# PassVault.net
KiCad netlist of a schematic drawn in EAGLE
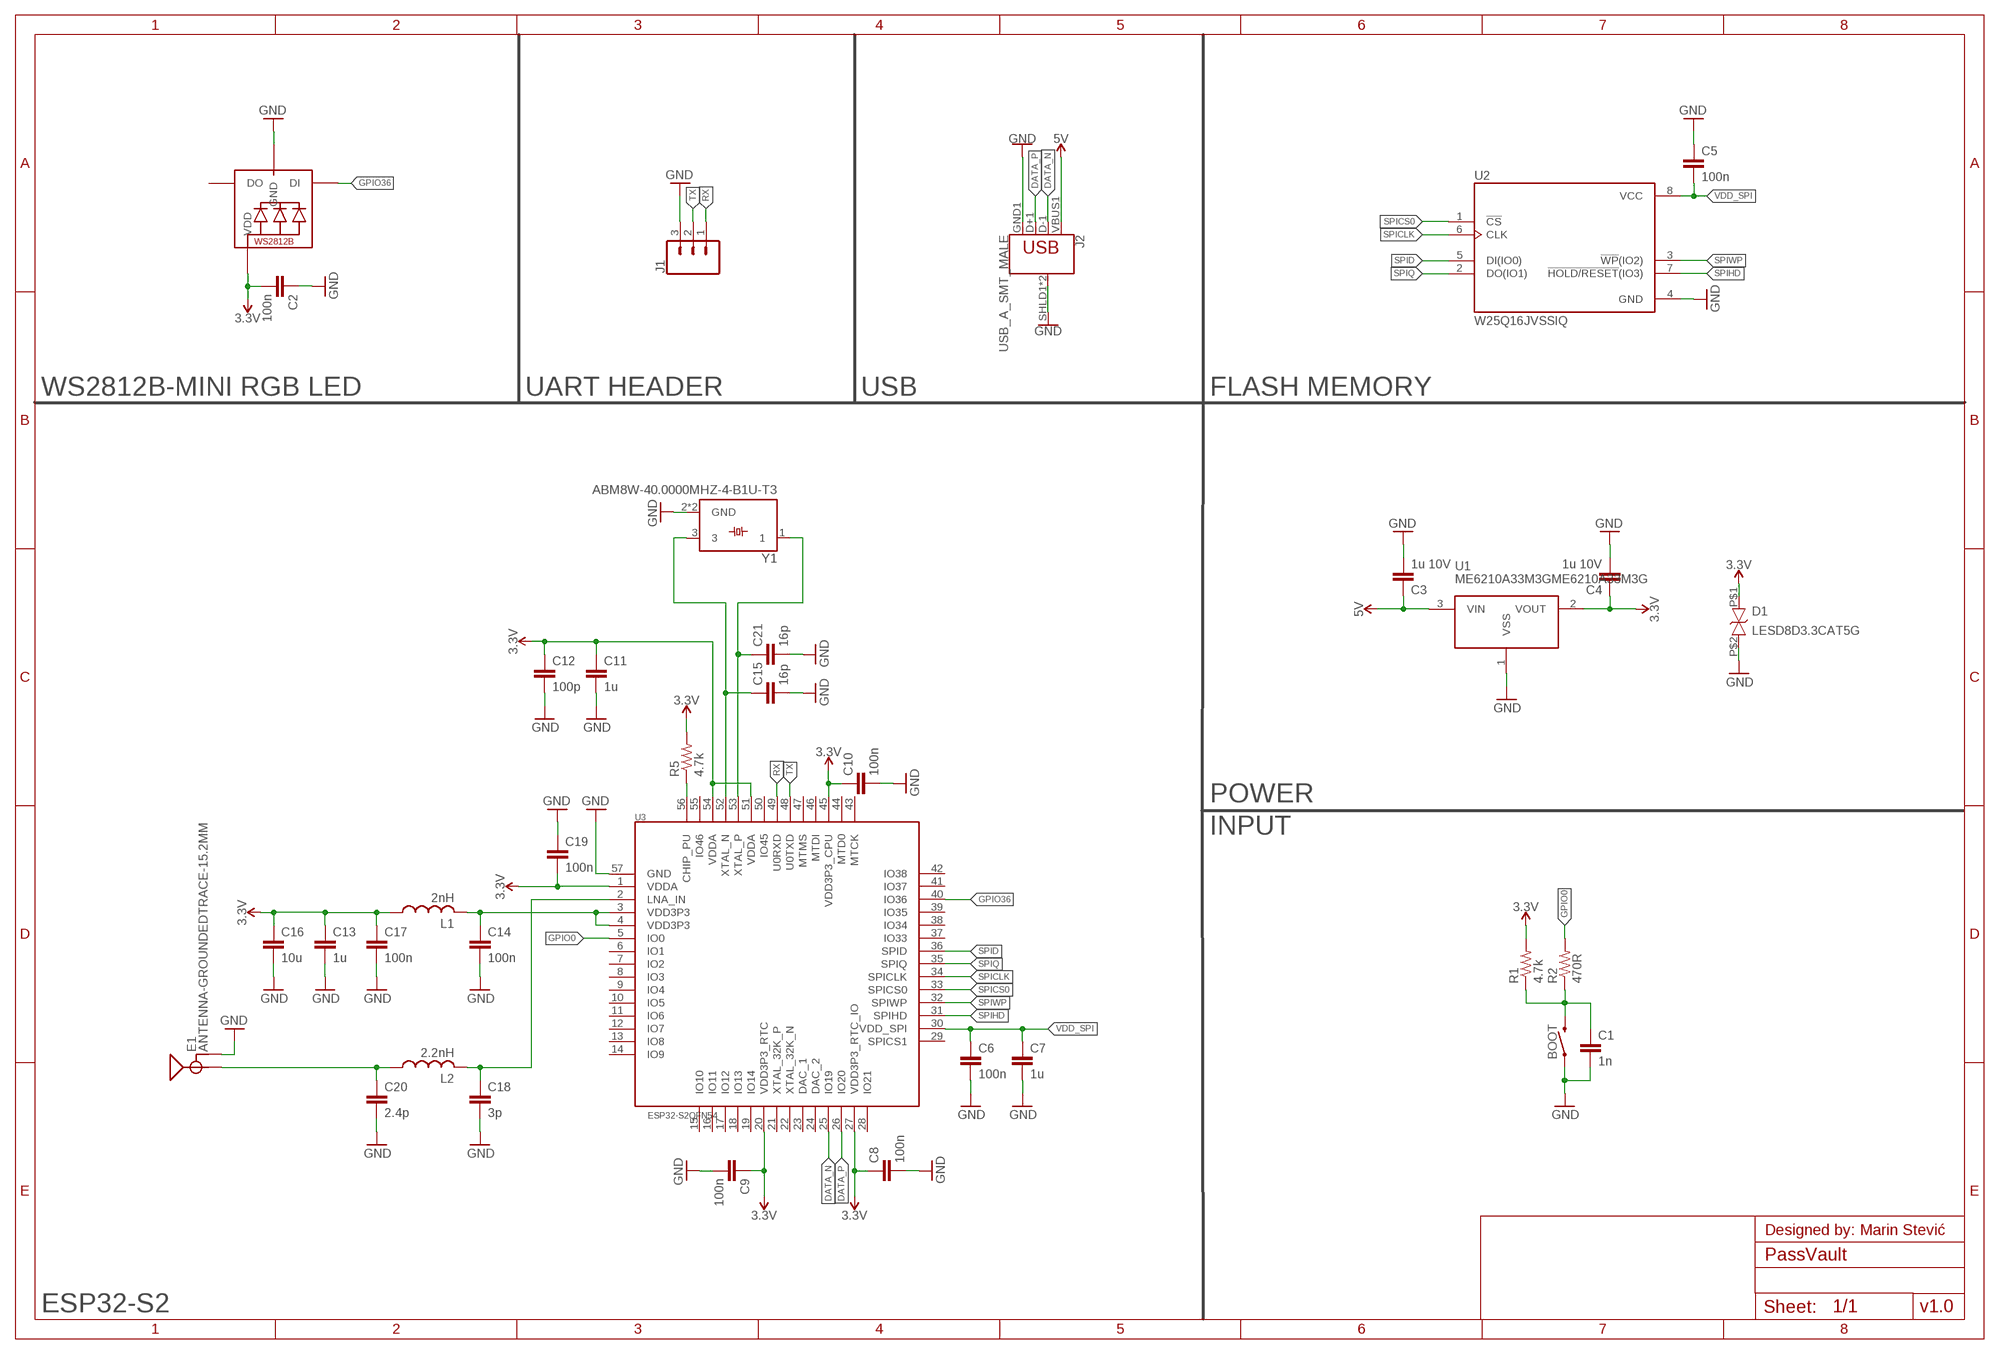
[diagram p0: schematic, sheet 1]

(export (version "E")
  (design (tool "Eeschema 10.0.6"))
  (components
    (comp (ref "BOOT")
      (value "MOMENTARY-SWITCH-SPST-SMD-12MM")
      (footprint "eagle-import:TACTILE_SWITCH_SMD_12MM")
      (libsource (lib "eagle-import") (part "MOMENTARY-SWITCH-SPST-SMD-12MM"))
    )
    (comp (ref "C1")
      (value "1n")
      (footprint "eagle-import:C0201")
      (libsource (lib "eagle-import") (part "C-EUC0201"))
    )
    (comp (ref "C2")
      (value "100n")
      (footprint "eagle-import:C0402")
      (libsource (lib "eagle-import") (part "C-EUC0402"))
    )
    (comp (ref "C3")
      (value "1u 10V")
      (footprint "eagle-import:C0402")
      (libsource (lib "eagle-import") (part "C-EUC0402"))
    )
    (comp (ref "C4")
      (value "1u 10V")
      (footprint "eagle-import:C0402")
      (libsource (lib "eagle-import") (part "C-EUC0402"))
    )
    (comp (ref "C5")
      (value "100n")
      (footprint "eagle-import:C0201")
      (libsource (lib "eagle-import") (part "C-EUC0201"))
    )
    (comp (ref "C6")
      (value "100n")
      (footprint "eagle-import:C0201")
      (libsource (lib "eagle-import") (part "C-EUC0201"))
    )
    (comp (ref "C7")
      (value "1u")
      (footprint "eagle-import:C0201")
      (libsource (lib "eagle-import") (part "C-EUC0201"))
    )
    (comp (ref "C8")
      (value "100n")
      (footprint "eagle-import:C0201")
      (libsource (lib "eagle-import") (part "C-EUC0201"))
    )
    (comp (ref "C9")
      (value "100n")
      (footprint "eagle-import:C0201")
      (libsource (lib "eagle-import") (part "C-EUC0201"))
    )
    (comp (ref "C10")
      (value "100n")
      (footprint "eagle-import:C0201")
      (libsource (lib "eagle-import") (part "C-EUC0201"))
    )
    (comp (ref "C11")
      (value "1u")
      (footprint "eagle-import:C0201")
      (libsource (lib "eagle-import") (part "C-EUC0201"))
    )
    (comp (ref "C12")
      (value "100p")
      (footprint "eagle-import:C0201")
      (libsource (lib "eagle-import") (part "C-EUC0201"))
    )
    (comp (ref "C13")
      (value "1u")
      (footprint "eagle-import:C0201")
      (libsource (lib "eagle-import") (part "C-EUC0201"))
    )
    (comp (ref "C14")
      (value "100n")
      (footprint "eagle-import:C0201")
      (libsource (lib "eagle-import") (part "C-EUC0201"))
    )
    (comp (ref "C15")
      (value "16p")
      (footprint "eagle-import:C0201")
      (libsource (lib "eagle-import") (part "C-EUC0201"))
    )
    (comp (ref "C16")
      (value "10u")
      (footprint "eagle-import:C0402")
      (libsource (lib "eagle-import") (part "C-EUC0402"))
    )
    (comp (ref "C17")
      (value "100n")
      (footprint "eagle-import:C0201")
      (libsource (lib "eagle-import") (part "C-EUC0201"))
    )
    (comp (ref "C18")
      (value "3p")
      (footprint "eagle-import:C0201")
      (libsource (lib "eagle-import") (part "C-EUC0201"))
    )
    (comp (ref "C19")
      (value "100n")
      (footprint "eagle-import:C0201")
      (libsource (lib "eagle-import") (part "C-EUC0201"))
    )
    (comp (ref "C20")
      (value "2.4p")
      (footprint "eagle-import:C0201")
      (libsource (lib "eagle-import") (part "C-EUC0201"))
    )
    (comp (ref "C21")
      (value "16p")
      (footprint "eagle-import:C0201")
      (libsource (lib "eagle-import") (part "C-EUC0201"))
    )
    (comp (ref "D1")
      (value "LESD8D3.3CAT5G")
      (footprint "eagle-import:LESD8D3.3CAT5G")
      (libsource (lib "eagle-import") (part "LESD8D3.3CAT5G"))
    )
    (comp (ref "E1")
      (value "ANTENNA-GROUNDEDTRACE-15.2MM")
      (footprint "eagle-import:TRACE_ANTENNA_2.4GHZ_15.2MM")
      (libsource (lib "eagle-import") (part "ANTENNA-GROUNDEDTRACE-15.2MM"))
    )
    (comp (ref "J1")
      (value "CONN_03")
      (footprint "eagle-import:1X03")
      (libsource (lib "eagle-import") (part "CONN_03"))
    )
    (comp (ref "J2")
      (value "USB_A_SMT_MALE")
      (footprint "eagle-import:USB-A-SMT-MALE")
      (libsource (lib "eagle-import") (part "USB_A_SMT_MALE"))
    )
    (comp (ref "L1")
      (value "2nH")
      (footprint "eagle-import:L0201")
      (libsource (lib "eagle-import") (part "L-USL0201"))
    )
    (comp (ref "L2")
      (value "2.2nH")
      (footprint "eagle-import:L0201")
      (libsource (lib "eagle-import") (part "L-USL0201"))
    )
    (comp (ref "LED1")
      (value "WS2812B3535")
      (footprint "eagle-import:LED3535")
      (fields (field (name "MF") "SparkFun Electronics") (field (name "MP") "WS2812B"))
      (libsource (lib "eagle-import") (part "WS2812B3535"))
    )
    (comp (ref "R1")
      (value "4.7k")
      (footprint "eagle-import:R0201")
      (libsource (lib "eagle-import") (part "R-US_R0201"))
    )
    (comp (ref "R2")
      (value "470R")
      (footprint "eagle-import:R0201")
      (libsource (lib "eagle-import") (part "R-US_R0201"))
    )
    (comp (ref "R5")
      (value "4.7k")
      (footprint "eagle-import:R0201")
      (libsource (lib "eagle-import") (part "R-US_R0201"))
    )
    (comp (ref "U1")
      (value "ME6210A33M3GME6210A33M3G")
      (footprint "eagle-import:SOT95P280X110-3N")
      (libsource (lib "eagle-import") (part "ME6210A33M3GME6210A33M3G"))
    )
    (comp (ref "U2")
      (value "W25Q16JVSSIQ")
      (footprint "eagle-import:SOIC127P790X216-8N")
      (fields (field (name "MF") "Winbond Electronics"))
      (libsource (lib "eagle-import") (part "W25Q16JVSSIQ"))
    )
    (comp (ref "U3")
      (value "ESP32-S2QFN54")
      (footprint "eagle-import:QFN40P700X700X90-57T400N")
      (fields (field (name "MF") "Espressif Systems") (field (name "MP") "ESP32-S2"))
      (libsource (lib "eagle-import") (part "ESP32-S2QFN54"))
    )
    (comp (ref "Y1")
      (value "ABM8W-40.0000MHZ-4-B1U-T3")
      (footprint "eagle-import:OSCSC320X250X100N")
      (fields (field (name "MF") "Abracon"))
      (libsource (lib "eagle-import") (part "ABM8W-40.0000MHZ-4-B1U-T3"))
    )
  )
  (nets
    (net (code "1") (name "3.3V") (class "Default")
      (node (ref "C10") (pin "1") (pinfunction "1_1") (pintype "passive"))
      (node (ref "C11") (pin "1") (pinfunction "1_1") (pintype "passive"))
      (node (ref "C12") (pin "1") (pinfunction "1_1") (pintype "passive"))
      (node (ref "C13") (pin "1") (pinfunction "1_1") (pintype "passive"))
      (node (ref "C16") (pin "1") (pinfunction "1_1") (pintype "passive"))
      (node (ref "C17") (pin "1") (pinfunction "1_1") (pintype "passive"))
      (node (ref "C19") (pin "2") (pinfunction "2_2") (pintype "passive"))
      (node (ref "C2") (pin "2") (pinfunction "2_2") (pintype "passive"))
      (node (ref "C4") (pin "1") (pinfunction "1_1") (pintype "passive"))
      (node (ref "C8") (pin "1") (pinfunction "1_1") (pintype "passive"))
      (node (ref "C9") (pin "1") (pinfunction "1_1") (pintype "passive"))
      (node (ref "D1") (pin "P$1") (pinfunction "P$1_P$1") (pintype "bidirectional"))
      (node (ref "L1") (pin "1") (pinfunction "1_1") (pintype "passive"))
      (node (ref "LED1") (pin "1") (pinfunction "VDD_1") (pintype "power_in"))
      (node (ref "R1") (pin "2") (pinfunction "2_2") (pintype "passive"))
      (node (ref "R5") (pin "2") (pinfunction "2_2") (pintype "passive"))
      (node (ref "U1") (pin "2") (pinfunction "VOUT_2") (pintype "bidirectional"))
      (node (ref "U3") (pin "1") (pinfunction "VDDA_1") (pintype "power_in"))
      (node (ref "U3") (pin "20") (pinfunction "VDD3P3_RTC_20") (pintype "power_in"))
      (node (ref "U3") (pin "27") (pinfunction "VDD3P3_RTC_IO_27") (pintype "power_in"))
      (node (ref "U3") (pin "45") (pinfunction "VDD3P3_CPU_45") (pintype "power_in"))
      (node (ref "U3") (pin "51") (pinfunction "VDDA_51") (pintype "power_in"))
      (node (ref "U3") (pin "54") (pinfunction "VDDA_54") (pintype "power_in"))
    )
    (net (code "2") (name "5V") (class "Default")
      (node (ref "C3") (pin "1") (pinfunction "1_1") (pintype "passive"))
      (node (ref "J2") (pin "VBUS1") (pinfunction "VBUS_VBUS1") (pintype "power_in"))
      (node (ref "U1") (pin "3") (pinfunction "VIN_3") (pintype "bidirectional"))
    )
    (net (code "3") (name "DATA_N") (class "Default")
      (node (ref "J2") (pin "D-1") (pinfunction "D-_D-1") (pintype "bidirectional"))
      (node (ref "U3") (pin "25") (pinfunction "IO19_25") (pintype "bidirectional"))
    )
    (net (code "4") (name "DATA_P") (class "Default")
      (node (ref "J2") (pin "D+1") (pinfunction "D+_D+1") (pintype "bidirectional"))
      (node (ref "U3") (pin "26") (pinfunction "IO20_26") (pintype "bidirectional"))
    )
    (net (code "5") (name "GND") (class "Default")
      (node (ref "BOOT") (pin "1") (pinfunction "1_1") (pintype "passive"))
      (node (ref "C1") (pin "2") (pinfunction "2_2") (pintype "passive"))
      (node (ref "C10") (pin "2") (pinfunction "2_2") (pintype "passive"))
      (node (ref "C11") (pin "2") (pinfunction "2_2") (pintype "passive"))
      (node (ref "C12") (pin "2") (pinfunction "2_2") (pintype "passive"))
      (node (ref "C13") (pin "2") (pinfunction "2_2") (pintype "passive"))
      (node (ref "C14") (pin "2") (pinfunction "2_2") (pintype "passive"))
      (node (ref "C15") (pin "2") (pinfunction "2_2") (pintype "passive"))
      (node (ref "C16") (pin "2") (pinfunction "2_2") (pintype "passive"))
      (node (ref "C17") (pin "2") (pinfunction "2_2") (pintype "passive"))
      (node (ref "C18") (pin "2") (pinfunction "2_2") (pintype "passive"))
      (node (ref "C19") (pin "1") (pinfunction "1_1") (pintype "passive"))
      (node (ref "C2") (pin "1") (pinfunction "1_1") (pintype "passive"))
      (node (ref "C20") (pin "2") (pinfunction "2_2") (pintype "passive"))
      (node (ref "C21") (pin "2") (pinfunction "2_2") (pintype "passive"))
      (node (ref "C3") (pin "2") (pinfunction "2_2") (pintype "passive"))
      (node (ref "C4") (pin "2") (pinfunction "2_2") (pintype "passive"))
      (node (ref "C5") (pin "1") (pinfunction "1_1") (pintype "passive"))
      (node (ref "C6") (pin "2") (pinfunction "2_2") (pintype "passive"))
      (node (ref "C7") (pin "2") (pinfunction "2_2") (pintype "passive"))
      (node (ref "C8") (pin "2") (pinfunction "2_2") (pintype "passive"))
      (node (ref "C9") (pin "2") (pinfunction "2_2") (pintype "passive"))
      (node (ref "D1") (pin "P$2") (pinfunction "P$2_P$2") (pintype "bidirectional"))
      (node (ref "E1") (pin "GND") (pinfunction "GND_GND") (pintype "bidirectional"))
      (node (ref "J1") (pin "3") (pinfunction "3_3") (pintype "passive"))
      (node (ref "J2") (pin "GND1") (pinfunction "GND_GND1") (pintype "power_in"))
      (node (ref "J2") (pin "SHLD1") (pinfunction "SHIELD_SHLD1") (pintype "bidirectional"))
      (node (ref "J2") (pin "SHLD2") (pinfunction "SHIELD_SHLD2") (pintype "bidirectional"))
      (node (ref "LED1") (pin "3") (pinfunction "GND_3") (pintype "power_in"))
      (node (ref "U1") (pin "1") (pinfunction "VSS_1") (pintype "bidirectional"))
      (node (ref "U2") (pin "4") (pinfunction "GND_4") (pintype "power_in"))
      (node (ref "U3") (pin "57") (pinfunction "GND_57") (pintype "power_in"))
      (node (ref "Y1") (pin "2") (pinfunction "GND_2") (pintype "power_in"))
      (node (ref "Y1") (pin "4") (pinfunction "GND_4") (pintype "power_in"))
    )
    (net (code "6") (name "GPIO0") (class "Default")
      (node (ref "R2") (pin "2") (pinfunction "2_2") (pintype "passive"))
      (node (ref "U3") (pin "5") (pinfunction "IO0_5") (pintype "bidirectional"))
    )
    (net (code "7") (name "GPIO36") (class "Default")
      (node (ref "LED1") (pin "4") (pinfunction "DI_4") (pintype "input"))
      (node (ref "U3") (pin "40") (pinfunction "IO36_40") (pintype "bidirectional"))
    )
    (net (code "8") (name "Net-(BOOT-2)") (class "Default")
      (node (ref "BOOT") (pin "3") (pinfunction "2_3") (pintype "passive"))
      (node (ref "C1") (pin "1") (pinfunction "1_1") (pintype "passive"))
      (node (ref "R1") (pin "1") (pinfunction "1_1") (pintype "passive"))
      (node (ref "R2") (pin "1") (pinfunction "1_1") (pintype "passive"))
    )
    (net (code "9") (name "Net-(C14-Pad1)") (class "Default")
      (node (ref "C14") (pin "1") (pinfunction "1_1") (pintype "passive"))
      (node (ref "L1") (pin "2") (pinfunction "2_2") (pintype "passive"))
      (node (ref "U3") (pin "3") (pinfunction "VDD3P3_3") (pintype "power_in"))
      (node (ref "U3") (pin "4") (pinfunction "VDD3P3_4") (pintype "power_in"))
    )
    (net (code "10") (name "Net-(E1-SIGNAL)") (class "Default")
      (node (ref "C20") (pin "1") (pinfunction "1_1") (pintype "passive"))
      (node (ref "E1") (pin "ANT") (pinfunction "SIGNAL_ANT") (pintype "bidirectional"))
      (node (ref "L2") (pin "1") (pinfunction "1_1") (pintype "passive"))
    )
    (net (code "11") (name "Net-(U3-CHIP_PU)") (class "Default")
      (node (ref "R5") (pin "1") (pinfunction "1_1") (pintype "passive"))
      (node (ref "U3") (pin "56") (pinfunction "CHIP_PU_56") (pintype "input"))
    )
    (net (code "12") (name "Net-(U3-LNA_IN)") (class "Default")
      (node (ref "C18") (pin "1") (pinfunction "1_1") (pintype "passive"))
      (node (ref "L2") (pin "2") (pinfunction "2_2") (pintype "passive"))
      (node (ref "U3") (pin "2") (pinfunction "LNA_IN_2") (pintype "bidirectional"))
    )
    (net (code "13") (name "Net-(U3-XTAL_N)") (class "Default")
      (node (ref "C15") (pin "1") (pinfunction "1_1") (pintype "passive"))
      (node (ref "U3") (pin "52") (pinfunction "XTAL_N_52") (pintype "bidirectional"))
      (node (ref "Y1") (pin "3") (pinfunction "3_3") (pintype "passive"))
    )
    (net (code "14") (name "Net-(U3-XTAL_P)") (class "Default")
      (node (ref "C21") (pin "1") (pinfunction "1_1") (pintype "passive"))
      (node (ref "U3") (pin "53") (pinfunction "XTAL_P_53") (pintype "bidirectional"))
      (node (ref "Y1") (pin "1") (pinfunction "1_1") (pintype "passive"))
    )
    (net (code "15") (name "RX") (class "Default")
      (node (ref "J1") (pin "1") (pinfunction "1_1") (pintype "passive"))
      (node (ref "U3") (pin "49") (pinfunction "U0RXD_49") (pintype "bidirectional"))
    )
    (net (code "16") (name "SPICLK") (class "Default")
      (node (ref "U2") (pin "6") (pinfunction "CLK_6") (pintype "input"))
      (node (ref "U3") (pin "34") (pinfunction "SPICLK_34") (pintype "bidirectional"))
    )
    (net (code "17") (name "SPICS0") (class "Default")
      (node (ref "U2") (pin "1") (pinfunction "~{CS}_1") (pintype "input"))
      (node (ref "U3") (pin "33") (pinfunction "SPICS0_33") (pintype "bidirectional"))
    )
    (net (code "18") (name "SPID") (class "Default")
      (node (ref "U2") (pin "5") (pinfunction "DI(IO0)_5") (pintype "bidirectional"))
      (node (ref "U3") (pin "36") (pinfunction "SPID_36") (pintype "bidirectional"))
    )
    (net (code "19") (name "SPIHD") (class "Default")
      (node (ref "U2") (pin "7") (pinfunction "~{HOLD/RESET}(IO3)_7") (pintype "bidirectional"))
      (node (ref "U3") (pin "31") (pinfunction "SPIHD_31") (pintype "bidirectional"))
    )
    (net (code "20") (name "SPIQ") (class "Default")
      (node (ref "U2") (pin "2") (pinfunction "DO(IO1)_2") (pintype "bidirectional"))
      (node (ref "U3") (pin "35") (pinfunction "SPIQ_35") (pintype "bidirectional"))
    )
    (net (code "21") (name "SPIWP") (class "Default")
      (node (ref "U2") (pin "3") (pinfunction "~{WP}(IO2)_3") (pintype "bidirectional"))
      (node (ref "U3") (pin "32") (pinfunction "SPIWP_32") (pintype "bidirectional"))
    )
    (net (code "22") (name "TX") (class "Default")
      (node (ref "J1") (pin "2") (pinfunction "2_2") (pintype "passive"))
      (node (ref "U3") (pin "48") (pinfunction "U0TXD_48") (pintype "bidirectional"))
    )
    (net (code "23") (name "VDD_SPI") (class "Default")
      (node (ref "C5") (pin "2") (pinfunction "2_2") (pintype "passive"))
      (node (ref "C6") (pin "1") (pinfunction "1_1") (pintype "passive"))
      (node (ref "C7") (pin "1") (pinfunction "1_1") (pintype "passive"))
      (node (ref "U2") (pin "8") (pinfunction "VCC_8") (pintype "power_in"))
      (node (ref "U3") (pin "30") (pinfunction "VDD_SPI_30") (pintype "power_in"))
    )
    (net (code "24") (name "unconnected-(LED1-DO-Pad2)") (class "Default")
      (node (ref "LED1") (pin "2") (pinfunction "DO_2") (pintype "output"))
    )
    (net (code "25") (name "unconnected-(U3-DAC_1-Pad23)") (class "Default")
      (node (ref "U3") (pin "23") (pinfunction "DAC_1_23") (pintype "bidirectional"))
    )
    (net (code "26") (name "unconnected-(U3-DAC_2-Pad24)") (class "Default")
      (node (ref "U3") (pin "24") (pinfunction "DAC_2_24") (pintype "bidirectional"))
    )
    (net (code "27") (name "unconnected-(U3-IO1-Pad6)") (class "Default")
      (node (ref "U3") (pin "6") (pinfunction "IO1_6") (pintype "bidirectional"))
    )
    (net (code "28") (name "unconnected-(U3-IO2-Pad7)") (class "Default")
      (node (ref "U3") (pin "7") (pinfunction "IO2_7") (pintype "bidirectional"))
    )
    (net (code "29") (name "unconnected-(U3-IO3-Pad8)") (class "Default")
      (node (ref "U3") (pin "8") (pinfunction "IO3_8") (pintype "bidirectional"))
    )
    (net (code "30") (name "unconnected-(U3-IO4-Pad9)") (class "Default")
      (node (ref "U3") (pin "9") (pinfunction "IO4_9") (pintype "bidirectional"))
    )
    (net (code "31") (name "unconnected-(U3-IO5-Pad10)") (class "Default")
      (node (ref "U3") (pin "10") (pinfunction "IO5_10") (pintype "bidirectional"))
    )
    (net (code "32") (name "unconnected-(U3-IO6-Pad11)") (class "Default")
      (node (ref "U3") (pin "11") (pinfunction "IO6_11") (pintype "bidirectional"))
    )
    (net (code "33") (name "unconnected-(U3-IO7-Pad12)") (class "Default")
      (node (ref "U3") (pin "12") (pinfunction "IO7_12") (pintype "bidirectional"))
    )
    (net (code "34") (name "unconnected-(U3-IO8-Pad13)") (class "Default")
      (node (ref "U3") (pin "13") (pinfunction "IO8_13") (pintype "bidirectional"))
    )
    (net (code "35") (name "unconnected-(U3-IO9-Pad14)") (class "Default")
      (node (ref "U3") (pin "14") (pinfunction "IO9_14") (pintype "bidirectional"))
    )
    (net (code "36") (name "unconnected-(U3-IO10-Pad15)") (class "Default")
      (node (ref "U3") (pin "15") (pinfunction "IO10_15") (pintype "bidirectional"))
    )
    (net (code "37") (name "unconnected-(U3-IO11-Pad16)") (class "Default")
      (node (ref "U3") (pin "16") (pinfunction "IO11_16") (pintype "bidirectional"))
    )
    (net (code "38") (name "unconnected-(U3-IO12-Pad17)") (class "Default")
      (node (ref "U3") (pin "17") (pinfunction "IO12_17") (pintype "bidirectional"))
    )
    (net (code "39") (name "unconnected-(U3-IO13-Pad18)") (class "Default")
      (node (ref "U3") (pin "18") (pinfunction "IO13_18") (pintype "bidirectional"))
    )
    (net (code "40") (name "unconnected-(U3-IO14-Pad19)") (class "Default")
      (node (ref "U3") (pin "19") (pinfunction "IO14_19") (pintype "bidirectional"))
    )
    (net (code "41") (name "unconnected-(U3-IO21-Pad28)") (class "Default")
      (node (ref "U3") (pin "28") (pinfunction "IO21_28") (pintype "bidirectional"))
    )
    (net (code "42") (name "unconnected-(U3-IO33-Pad37)") (class "Default")
      (node (ref "U3") (pin "37") (pinfunction "IO33_37") (pintype "bidirectional"))
    )
    (net (code "43") (name "unconnected-(U3-IO34-Pad38)") (class "Default")
      (node (ref "U3") (pin "38") (pinfunction "IO34_38") (pintype "bidirectional"))
    )
    (net (code "44") (name "unconnected-(U3-IO35-Pad39)") (class "Default")
      (node (ref "U3") (pin "39") (pinfunction "IO35_39") (pintype "bidirectional"))
    )
    (net (code "45") (name "unconnected-(U3-IO37-Pad41)") (class "Default")
      (node (ref "U3") (pin "41") (pinfunction "IO37_41") (pintype "bidirectional"))
    )
    (net (code "46") (name "unconnected-(U3-IO38-Pad42)") (class "Default")
      (node (ref "U3") (pin "42") (pinfunction "IO38_42") (pintype "bidirectional"))
    )
    (net (code "47") (name "unconnected-(U3-IO45-Pad50)") (class "Default")
      (node (ref "U3") (pin "50") (pinfunction "IO45_50") (pintype "bidirectional"))
    )
    (net (code "48") (name "unconnected-(U3-IO46-Pad55)") (class "Default")
      (node (ref "U3") (pin "55") (pinfunction "IO46_55") (pintype "input"))
    )
    (net (code "49") (name "unconnected-(U3-MTCK-Pad43)") (class "Default")
      (node (ref "U3") (pin "43") (pinfunction "MTCK_43") (pintype "bidirectional"))
    )
    (net (code "50") (name "unconnected-(U3-MTD0-Pad44)") (class "Default")
      (node (ref "U3") (pin "44") (pinfunction "MTD0_44") (pintype "bidirectional"))
    )
    (net (code "51") (name "unconnected-(U3-MTDI-Pad46)") (class "Default")
      (node (ref "U3") (pin "46") (pinfunction "MTDI_46") (pintype "bidirectional"))
    )
    (net (code "52") (name "unconnected-(U3-MTMS-Pad47)") (class "Default")
      (node (ref "U3") (pin "47") (pinfunction "MTMS_47") (pintype "bidirectional"))
    )
    (net (code "53") (name "unconnected-(U3-SPICS1-Pad29)") (class "Default")
      (node (ref "U3") (pin "29") (pinfunction "SPICS1_29") (pintype "bidirectional"))
    )
    (net (code "54") (name "unconnected-(U3-XTAL_32K_N-Pad22)") (class "Default")
      (node (ref "U3") (pin "22") (pinfunction "XTAL_32K_N_22") (pintype "bidirectional"))
    )
    (net (code "55") (name "unconnected-(U3-XTAL_32K_P-Pad21)") (class "Default")
      (node (ref "U3") (pin "21") (pinfunction "XTAL_32K_P_21") (pintype "bidirectional"))
    )
  )
)
